# final.net
KiCad netlist of a schematic drawn in EAGLE
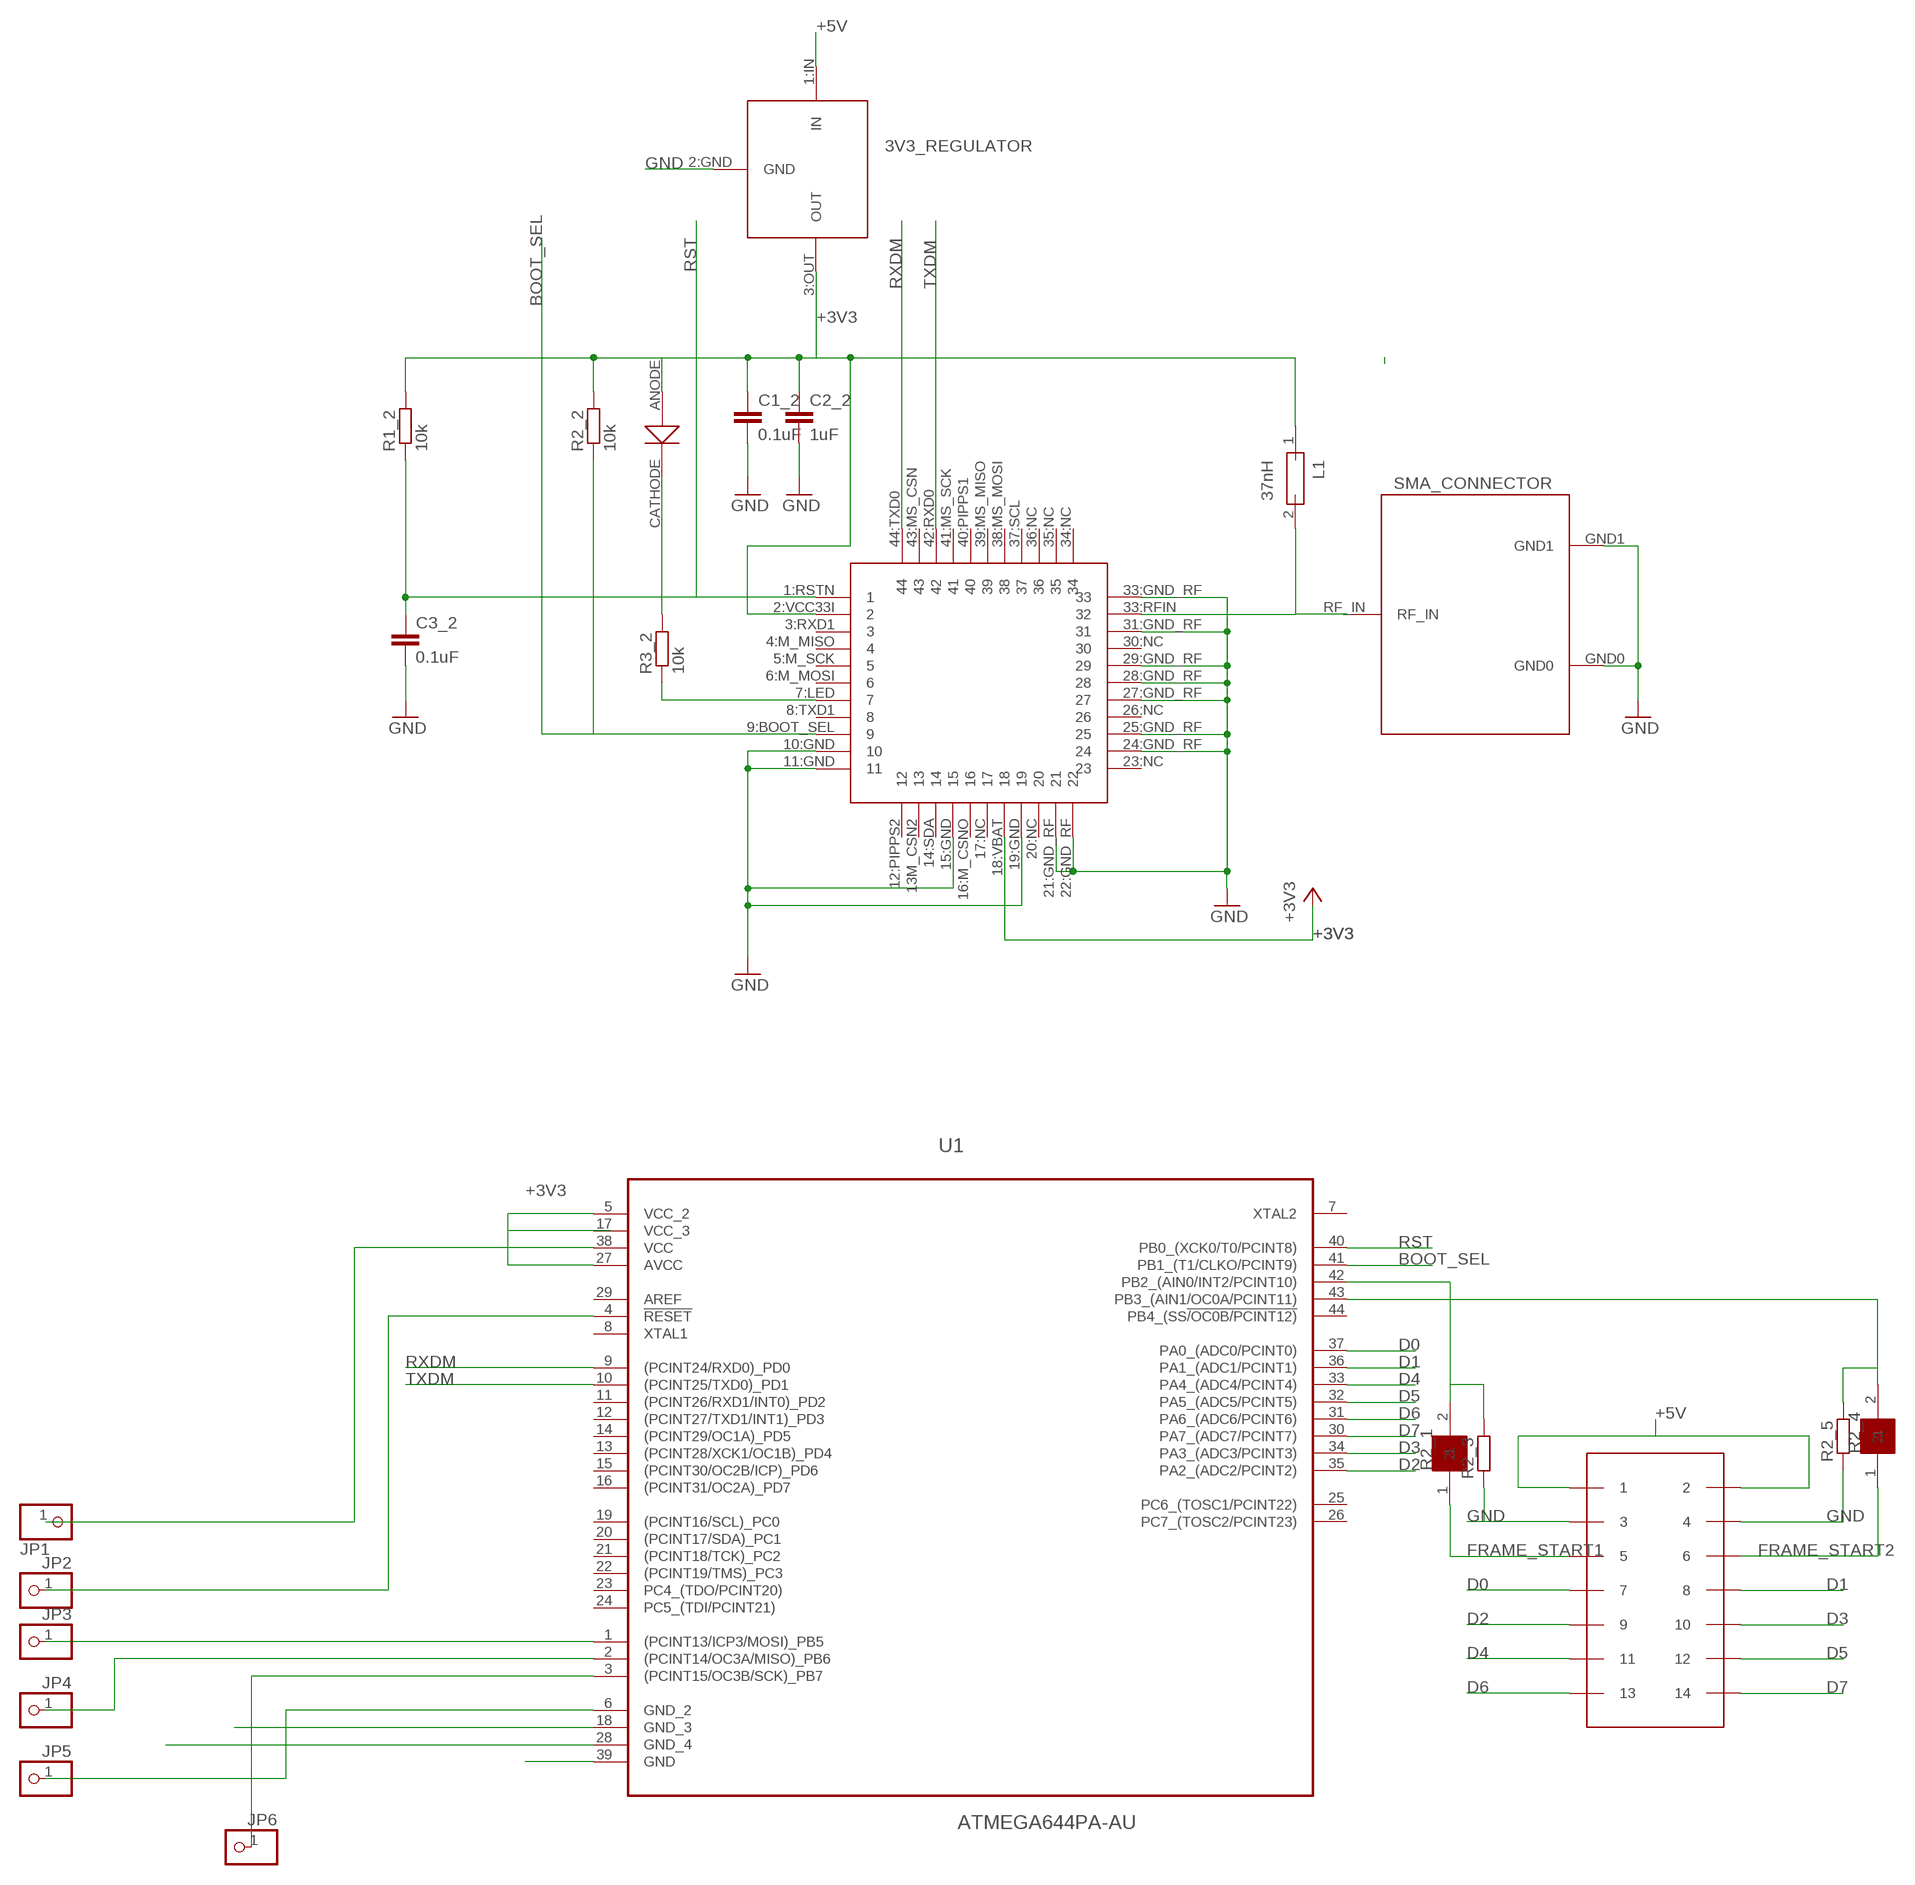
[diagram p0: schematic, sheet 1]

(export (version "E")
  (design (tool "Eeschema 10.0.6"))
  (components
    (comp (ref "3V3_REGULATOR")
      (value "LM3940IT-3.3/NOPB")
      (footprint "eagle-import:3PIN")
      (libsource (lib "eagle-import") (part "LM3940IT-3.3/NOPB"))
    )
    (comp (ref "C1_2")
      (value "0.1uF")
      (footprint "eagle-import:C0402")
      (libsource (lib "eagle-import") (part "C-EUC0402"))
    )
    (comp (ref "C2_2")
      (value "1uF")
      (footprint "eagle-import:C0402")
      (libsource (lib "eagle-import") (part "C-EUC0402"))
    )
    (comp (ref "C3_2")
      (value "0.1uF")
      (footprint "eagle-import:C0402")
      (libsource (lib "eagle-import") (part "C-EUC0402"))
    )
    (comp (ref "GPS_1")
      (value "VENUS838FLPX")
      (footprint "eagle-import:LGA-44")
      (libsource (lib "eagle-import") (part "VENUS838FLPX"))
    )
    (comp (ref "HARWIN_CONNECTOR")
      (value "HARWIN_CONNECTOR")
      (footprint "eagle-import:14DIP")
      (libsource (lib "eagle-import") (part "HARWIN_CONNECTOR"))
    )
    (comp (ref "JP1")
      (value "PINHD-1X1")
      (footprint "eagle-import:1X01")
      (libsource (lib "eagle-import") (part "PINHD-1X1"))
    )
    (comp (ref "JP2")
      (value "PINHD-1X1")
      (footprint "eagle-import:1X01")
      (libsource (lib "eagle-import") (part "PINHD-1X1"))
    )
    (comp (ref "JP3")
      (value "PINHD-1X1")
      (footprint "eagle-import:1X01")
      (libsource (lib "eagle-import") (part "PINHD-1X1"))
    )
    (comp (ref "JP4")
      (value "PINHD-1X1")
      (footprint "eagle-import:1X01")
      (libsource (lib "eagle-import") (part "PINHD-1X1"))
    )
    (comp (ref "JP5")
      (value "PINHD-1X1")
      (footprint "eagle-import:1X01")
      (libsource (lib "eagle-import") (part "PINHD-1X1"))
    )
    (comp (ref "JP6")
      (value "PINHD-1X1")
      (footprint "eagle-import:1X01")
      (libsource (lib "eagle-import") (part "PINHD-1X1"))
    )
    (comp (ref "L1")
      (value "37nH")
      (footprint "eagle-import:0805")
      (libsource (lib "eagle-import") (part "0805_INDUCTOR"))
    )
    (comp (ref "R1_2")
      (value "10k")
      (footprint "eagle-import:R0402")
      (libsource (lib "eagle-import") (part "R-EU_R0402"))
    )
    (comp (ref "R2_1")
      (value "0805RESISTOR")
      (footprint "eagle-import:0805")
      (libsource (lib "eagle-import") (part "0805RESISTOR"))
    )
    (comp (ref "R2_2")
      (value "10k")
      (footprint "eagle-import:R0402")
      (libsource (lib "eagle-import") (part "R-EU_R0402"))
    )
    (comp (ref "R2_3")
      (value "R-EU_R0402")
      (footprint "eagle-import:R0402")
      (libsource (lib "eagle-import") (part "R-EU_R0402"))
    )
    (comp (ref "R2_4")
      (value "0805RESISTOR")
      (footprint "eagle-import:0805")
      (libsource (lib "eagle-import") (part "0805RESISTOR"))
    )
    (comp (ref "R2_5")
      (value "R-EU_R0402")
      (footprint "eagle-import:R0402")
      (libsource (lib "eagle-import") (part "R-EU_R0402"))
    )
    (comp (ref "R3_2")
      (value "10k")
      (footprint "eagle-import:R0402")
      (libsource (lib "eagle-import") (part "R-EU_R0402"))
    )
    (comp (ref "SMA_CONNECTOR")
      (value "SMA_SIDE")
      (footprint "eagle-import:SMA_SIDE")
      (libsource (lib "eagle-import") (part "SMA_SIDE"))
    )
    (comp (ref "U$1")
      (value "HSMH-C190-DIODE")
      (footprint "eagle-import:HSMH-C190-DIODE")
      (libsource (lib "eagle-import") (part "HSMH-C190-DIODE"))
    )
    (comp (ref "U1")
      (value "ATMEGA644PA-AU")
      (footprint "eagle-import:QFP80P1200X1200X120-44N")
      (libsource (lib "eagle-import") (part "ATMEGA644PA-AU"))
    )
  )
  (nets
    (net (code "1") (name "+3V3") (class "Default")
      (node (ref "3V3_REGULATOR") (pin "3:OUT") (pinfunction "OUT_3:OUT") (pintype "bidirectional"))
      (node (ref "C1_2") (pin "1") (pinfunction "1_1") (pintype "passive"))
      (node (ref "C2_2") (pin "1") (pinfunction "1_1") (pintype "passive"))
      (node (ref "GPS_1") (pin "18:VBAT") (pinfunction "18_18:VBAT") (pintype "bidirectional"))
      (node (ref "GPS_1") (pin "2:VCC33I") (pinfunction "2_2:VCC33I") (pintype "bidirectional"))
      (node (ref "JP1") (pin "1") (pinfunction "1_1") (pintype "passive"))
      (node (ref "L1") (pin "1") (pinfunction "1_1") (pintype "bidirectional"))
      (node (ref "R1_2") (pin "2") (pinfunction "2_2") (pintype "passive"))
      (node (ref "R2_2") (pin "2") (pinfunction "2_2") (pintype "passive"))
      (node (ref "U$1") (pin "ANODE") (pinfunction "AN_ANODE") (pintype "bidirectional"))
      (node (ref "U1") (pin "17") (pinfunction "VCC_3_17") (pintype "power_in"))
      (node (ref "U1") (pin "27") (pinfunction "AVCC_27") (pintype "power_in"))
      (node (ref "U1") (pin "38") (pinfunction "VCC_38") (pintype "power_in"))
      (node (ref "U1") (pin "5") (pinfunction "VCC_2_5") (pintype "power_in"))
    )
    (net (code "2") (name "/+5V") (class "Default")
      (node (ref "3V3_REGULATOR") (pin "1:IN") (pinfunction "IN_1:IN") (pintype "bidirectional"))
      (node (ref "HARWIN_CONNECTOR") (pin "1") (pinfunction "1_1") (pintype "bidirectional"))
      (node (ref "HARWIN_CONNECTOR") (pin "2") (pinfunction "2_2") (pintype "bidirectional"))
    )
    (net (code "3") (name "/BOOT_SEL") (class "Default")
      (node (ref "GPS_1") (pin "9:BOOT_SEL") (pinfunction "9_9:BOOT_SEL") (pintype "bidirectional"))
      (node (ref "R2_2") (pin "1") (pinfunction "1_1") (pintype "passive"))
      (node (ref "U1") (pin "41") (pinfunction "PB1_(T1/CLKO/PCINT9)_41") (pintype "bidirectional"))
    )
    (net (code "4") (name "/D0") (class "Default")
      (node (ref "HARWIN_CONNECTOR") (pin "7") (pinfunction "7_7") (pintype "bidirectional"))
      (node (ref "U1") (pin "37") (pinfunction "PA0_(ADC0/PCINT0)_37") (pintype "bidirectional"))
    )
    (net (code "5") (name "/D1") (class "Default")
      (node (ref "HARWIN_CONNECTOR") (pin "8") (pinfunction "8_8") (pintype "bidirectional"))
      (node (ref "U1") (pin "36") (pinfunction "PA1_(ADC1/PCINT1)_36") (pintype "bidirectional"))
    )
    (net (code "6") (name "/D2") (class "Default")
      (node (ref "HARWIN_CONNECTOR") (pin "9") (pinfunction "9_9") (pintype "bidirectional"))
      (node (ref "U1") (pin "35") (pinfunction "PA2_(ADC2/PCINT2)_35") (pintype "bidirectional"))
    )
    (net (code "7") (name "/D3") (class "Default")
      (node (ref "HARWIN_CONNECTOR") (pin "10") (pinfunction "10_10") (pintype "bidirectional"))
      (node (ref "U1") (pin "34") (pinfunction "PA3_(ADC3/PCINT3)_34") (pintype "bidirectional"))
    )
    (net (code "8") (name "/D4") (class "Default")
      (node (ref "HARWIN_CONNECTOR") (pin "11") (pinfunction "11_11") (pintype "bidirectional"))
      (node (ref "U1") (pin "33") (pinfunction "PA4_(ADC4/PCINT4)_33") (pintype "bidirectional"))
    )
    (net (code "9") (name "/D5") (class "Default")
      (node (ref "HARWIN_CONNECTOR") (pin "12") (pinfunction "12_12") (pintype "bidirectional"))
      (node (ref "U1") (pin "32") (pinfunction "PA5_(ADC5/PCINT5)_32") (pintype "bidirectional"))
    )
    (net (code "10") (name "/D6") (class "Default")
      (node (ref "HARWIN_CONNECTOR") (pin "13") (pinfunction "13_13") (pintype "bidirectional"))
      (node (ref "U1") (pin "31") (pinfunction "PA6_(ADC6/PCINT6)_31") (pintype "bidirectional"))
    )
    (net (code "11") (name "/D7") (class "Default")
      (node (ref "HARWIN_CONNECTOR") (pin "14") (pinfunction "14_14") (pintype "bidirectional"))
      (node (ref "U1") (pin "30") (pinfunction "PA7_(ADC7/PCINT7)_30") (pintype "bidirectional"))
    )
    (net (code "12") (name "/FRAME_START1") (class "Default")
      (node (ref "HARWIN_CONNECTOR") (pin "5") (pinfunction "5_5") (pintype "bidirectional"))
      (node (ref "R2_1") (pin "1") (pinfunction "1_1") (pintype "bidirectional"))
    )
    (net (code "13") (name "/FRAME_START2") (class "Default")
      (node (ref "HARWIN_CONNECTOR") (pin "6") (pinfunction "6_6") (pintype "bidirectional"))
      (node (ref "R2_4") (pin "1") (pinfunction "1_1") (pintype "bidirectional"))
    )
    (net (code "14") (name "/RST") (class "Default")
      (node (ref "C3_2") (pin "1") (pinfunction "1_1") (pintype "passive"))
      (node (ref "GPS_1") (pin "1:RSTN") (pinfunction "1_1:RSTN") (pintype "bidirectional"))
      (node (ref "R1_2") (pin "1") (pinfunction "1_1") (pintype "passive"))
      (node (ref "U1") (pin "40") (pinfunction "PB0_(XCK0/T0/PCINT8)_40") (pintype "bidirectional"))
    )
    (net (code "15") (name "/RXDM") (class "Default")
      (node (ref "GPS_1") (pin "44:TXD0") (pinfunction "44_44:TXD0") (pintype "bidirectional"))
      (node (ref "U1") (pin "9") (pinfunction "(PCINT24/RXD0)_PD0_9") (pintype "bidirectional"))
    )
    (net (code "16") (name "/TXDM") (class "Default")
      (node (ref "GPS_1") (pin "42:RXD0") (pinfunction "42_42:RXD0") (pintype "bidirectional"))
      (node (ref "U1") (pin "10") (pinfunction "(PCINT25/TXD0)_PD1_10") (pintype "bidirectional"))
    )
    (net (code "17") (name "GND") (class "Default")
      (node (ref "3V3_REGULATOR") (pin "2:GND") (pinfunction "GND_2:GND") (pintype "bidirectional"))
      (node (ref "C1_2") (pin "2") (pinfunction "2_2") (pintype "passive"))
      (node (ref "C2_2") (pin "2") (pinfunction "2_2") (pintype "passive"))
      (node (ref "C3_2") (pin "2") (pinfunction "2_2") (pintype "passive"))
      (node (ref "GPS_1") (pin "10:GND") (pinfunction "10_10:GND") (pintype "bidirectional"))
      (node (ref "GPS_1") (pin "11:GND") (pinfunction "11_11:GND") (pintype "bidirectional"))
      (node (ref "GPS_1") (pin "15:GND") (pinfunction "15_15:GND") (pintype "bidirectional"))
      (node (ref "GPS_1") (pin "19:GND") (pinfunction "19_19:GND") (pintype "bidirectional"))
      (node (ref "GPS_1") (pin "21:GND_RF") (pinfunction "21_21:GND_RF") (pintype "bidirectional"))
      (node (ref "GPS_1") (pin "22:GND_RF") (pinfunction "22_22:GND_RF") (pintype "bidirectional"))
      (node (ref "GPS_1") (pin "24:GND_RF") (pinfunction "24_24:GND_RF") (pintype "bidirectional"))
      (node (ref "GPS_1") (pin "25:GND_RF") (pinfunction "25_25:GND_RF") (pintype "bidirectional"))
      (node (ref "GPS_1") (pin "27:GND_RF") (pinfunction "27_27:GND_RF") (pintype "bidirectional"))
      (node (ref "GPS_1") (pin "28:GND_RF") (pinfunction "28_28:GND_RF") (pintype "bidirectional"))
      (node (ref "GPS_1") (pin "29:GND_RF") (pinfunction "29_29:GND_RF") (pintype "bidirectional"))
      (node (ref "GPS_1") (pin "31:GND_RF") (pinfunction "31_31:GND_RF") (pintype "bidirectional"))
      (node (ref "GPS_1") (pin "33:GND_RF") (pinfunction "33_33:GND_RF") (pintype "bidirectional"))
      (node (ref "HARWIN_CONNECTOR") (pin "3") (pinfunction "3_3") (pintype "bidirectional"))
      (node (ref "HARWIN_CONNECTOR") (pin "4") (pinfunction "4_4") (pintype "bidirectional"))
      (node (ref "JP5") (pin "1") (pinfunction "1_1") (pintype "passive"))
      (node (ref "R2_3") (pin "1") (pinfunction "1_1") (pintype "passive"))
      (node (ref "R2_5") (pin "1") (pinfunction "1_1") (pintype "passive"))
      (node (ref "SMA_CONNECTOR") (pin "GND0") (pinfunction "GND0_GND0") (pintype "bidirectional"))
      (node (ref "SMA_CONNECTOR") (pin "GND1") (pinfunction "GND1_GND1") (pintype "bidirectional"))
      (node (ref "U1") (pin "18") (pinfunction "GND_3_18") (pintype "passive"))
      (node (ref "U1") (pin "28") (pinfunction "GND_4_28") (pintype "passive"))
      (node (ref "U1") (pin "39") (pinfunction "GND_39") (pintype "passive"))
      (node (ref "U1") (pin "6") (pinfunction "GND_2_6") (pintype "passive"))
    )
    (net (code "18") (name "Net-(GPS_1-7)") (class "Default")
      (node (ref "GPS_1") (pin "7:LED") (pinfunction "7_7:LED") (pintype "bidirectional"))
      (node (ref "R3_2") (pin "1") (pinfunction "1_1") (pintype "passive"))
    )
    (net (code "19") (name "Net-(GPS_1-32)") (class "Default")
      (node (ref "GPS_1") (pin "33:RFIN") (pinfunction "32_33:RFIN") (pintype "bidirectional"))
      (node (ref "L1") (pin "2") (pinfunction "2_2") (pintype "bidirectional"))
      (node (ref "SMA_CONNECTOR") (pin "RF_IN") (pinfunction "RF_IN_RF_IN") (pintype "bidirectional"))
    )
    (net (code "20") (name "Net-(U$1-CATH)") (class "Default")
      (node (ref "R3_2") (pin "2") (pinfunction "2_2") (pintype "passive"))
      (node (ref "U$1") (pin "CATHODE") (pinfunction "CATH_CATHODE") (pintype "bidirectional"))
    )
    (net (code "21") (name "Net-(U1-(PCINT13{slash}ICP3{slash}MOSI)_PB5)") (class "Default")
      (node (ref "JP3") (pin "1") (pinfunction "1_1") (pintype "passive"))
      (node (ref "U1") (pin "1") (pinfunction "(PCINT13/ICP3/MOSI)_PB5_1") (pintype "bidirectional"))
    )
    (net (code "22") (name "Net-(U1-(PCINT14{slash}OC3A{slash}MISO)_PB6)") (class "Default")
      (node (ref "JP4") (pin "1") (pinfunction "1_1") (pintype "passive"))
      (node (ref "U1") (pin "2") (pinfunction "(PCINT14/OC3A/MISO)_PB6_2") (pintype "bidirectional"))
    )
    (net (code "23") (name "Net-(U1-(PCINT15{slash}OC3B{slash}SCK)_PB7)") (class "Default")
      (node (ref "JP6") (pin "1") (pinfunction "1_1") (pintype "passive"))
      (node (ref "U1") (pin "3") (pinfunction "(PCINT15/OC3B/SCK)_PB7_3") (pintype "bidirectional"))
    )
    (net (code "24") (name "Net-(U1-PB2_(AIN0{slash}INT2{slash}PCINT10))") (class "Default")
      (node (ref "R2_1") (pin "2") (pinfunction "2_2") (pintype "bidirectional"))
      (node (ref "R2_3") (pin "2") (pinfunction "2_2") (pintype "passive"))
      (node (ref "U1") (pin "42") (pinfunction "PB2_(AIN0/INT2/PCINT10)_42") (pintype "bidirectional"))
    )
    (net (code "25") (name "Net-(U1-PB3_(AIN1{slash}OC0A{slash}PCINT11))") (class "Default")
      (node (ref "R2_4") (pin "2") (pinfunction "2_2") (pintype "bidirectional"))
      (node (ref "R2_5") (pin "2") (pinfunction "2_2") (pintype "passive"))
      (node (ref "U1") (pin "43") (pinfunction "PB3_(AIN1/OC0A/PCINT11)_43") (pintype "bidirectional"))
    )
    (net (code "26") (name "Net-(U1-~{RESET})") (class "Default")
      (node (ref "JP2") (pin "1") (pinfunction "1_1") (pintype "passive"))
      (node (ref "U1") (pin "4") (pinfunction "~{RESET}_4") (pintype "input"))
    )
    (net (code "27") (name "unconnected-(GPS_1-3-Pad3:RXD1)") (class "Default")
      (node (ref "GPS_1") (pin "3:RXD1") (pinfunction "3_3:RXD1") (pintype "bidirectional"))
    )
    (net (code "28") (name "unconnected-(GPS_1-4-Pad4:M_MISO)") (class "Default")
      (node (ref "GPS_1") (pin "4:M_MISO") (pinfunction "4_4:M_MISO") (pintype "bidirectional"))
    )
    (net (code "29") (name "unconnected-(GPS_1-5-Pad5:M_SCK)") (class "Default")
      (node (ref "GPS_1") (pin "5:M_SCK") (pinfunction "5_5:M_SCK") (pintype "bidirectional"))
    )
    (net (code "30") (name "unconnected-(GPS_1-6-Pad6:M_MOSI)") (class "Default")
      (node (ref "GPS_1") (pin "6:M_MOSI") (pinfunction "6_6:M_MOSI") (pintype "bidirectional"))
    )
    (net (code "31") (name "unconnected-(GPS_1-8-Pad8:TXD1)") (class "Default")
      (node (ref "GPS_1") (pin "8:TXD1") (pinfunction "8_8:TXD1") (pintype "bidirectional"))
    )
    (net (code "32") (name "unconnected-(GPS_1-12-Pad12:PIPPS2)") (class "Default")
      (node (ref "GPS_1") (pin "12:PIPPS2") (pinfunction "12_12:PIPPS2") (pintype "bidirectional"))
    )
    (net (code "33") (name "unconnected-(GPS_1-13-Pad13M_CSN2)") (class "Default")
      (node (ref "GPS_1") (pin "13M_CSN2") (pinfunction "13_13M_CSN2") (pintype "bidirectional"))
    )
    (net (code "34") (name "unconnected-(GPS_1-14-Pad14:SDA)") (class "Default")
      (node (ref "GPS_1") (pin "14:SDA") (pinfunction "14_14:SDA") (pintype "bidirectional"))
    )
    (net (code "35") (name "unconnected-(GPS_1-16-Pad16:M_CSNO)") (class "Default")
      (node (ref "GPS_1") (pin "16:M_CSNO") (pinfunction "16_16:M_CSNO") (pintype "bidirectional"))
    )
    (net (code "36") (name "unconnected-(GPS_1-17-Pad17:NC)") (class "Default")
      (node (ref "GPS_1") (pin "17:NC") (pinfunction "17_17:NC") (pintype "bidirectional"))
    )
    (net (code "37") (name "unconnected-(GPS_1-20-Pad20:NC)") (class "Default")
      (node (ref "GPS_1") (pin "20:NC") (pinfunction "20_20:NC") (pintype "bidirectional"))
    )
    (net (code "38") (name "unconnected-(GPS_1-23-Pad23:NC)") (class "Default")
      (node (ref "GPS_1") (pin "23:NC") (pinfunction "23_23:NC") (pintype "bidirectional"))
    )
    (net (code "39") (name "unconnected-(GPS_1-26-Pad26:NC)") (class "Default")
      (node (ref "GPS_1") (pin "26:NC") (pinfunction "26_26:NC") (pintype "bidirectional"))
    )
    (net (code "40") (name "unconnected-(GPS_1-30-Pad30:NC)") (class "Default")
      (node (ref "GPS_1") (pin "30:NC") (pinfunction "30_30:NC") (pintype "bidirectional"))
    )
    (net (code "41") (name "unconnected-(GPS_1-34-Pad34:NC)") (class "Default")
      (node (ref "GPS_1") (pin "34:NC") (pinfunction "34_34:NC") (pintype "bidirectional"))
    )
    (net (code "42") (name "unconnected-(GPS_1-35-Pad35:NC)") (class "Default")
      (node (ref "GPS_1") (pin "35:NC") (pinfunction "35_35:NC") (pintype "bidirectional"))
    )
    (net (code "43") (name "unconnected-(GPS_1-36-Pad36:NC)") (class "Default")
      (node (ref "GPS_1") (pin "36:NC") (pinfunction "36_36:NC") (pintype "bidirectional"))
    )
    (net (code "44") (name "unconnected-(GPS_1-37-Pad37:SCL)") (class "Default")
      (node (ref "GPS_1") (pin "37:SCL") (pinfunction "37_37:SCL") (pintype "bidirectional"))
    )
    (net (code "45") (name "unconnected-(GPS_1-38-Pad38:MS_MOSI)") (class "Default")
      (node (ref "GPS_1") (pin "38:MS_MOSI") (pinfunction "38_38:MS_MOSI") (pintype "bidirectional"))
    )
    (net (code "46") (name "unconnected-(GPS_1-39-Pad39:MS_MISO)") (class "Default")
      (node (ref "GPS_1") (pin "39:MS_MISO") (pinfunction "39_39:MS_MISO") (pintype "bidirectional"))
    )
    (net (code "47") (name "unconnected-(GPS_1-40-Pad40:PIPPS1)") (class "Default")
      (node (ref "GPS_1") (pin "40:PIPPS1") (pinfunction "40_40:PIPPS1") (pintype "bidirectional"))
    )
    (net (code "48") (name "unconnected-(GPS_1-41-Pad41:MS_SCK)") (class "Default")
      (node (ref "GPS_1") (pin "41:MS_SCK") (pinfunction "41_41:MS_SCK") (pintype "bidirectional"))
    )
    (net (code "49") (name "unconnected-(GPS_1-43-Pad43:MS_CSN)") (class "Default")
      (node (ref "GPS_1") (pin "43:MS_CSN") (pinfunction "43_43:MS_CSN") (pintype "bidirectional"))
    )
    (net (code "50") (name "unconnected-(U1-(PCINT16{slash}SCL)_PC0-Pad19)") (class "Default")
      (node (ref "U1") (pin "19") (pinfunction "(PCINT16/SCL)_PC0_19") (pintype "bidirectional"))
    )
    (net (code "51") (name "unconnected-(U1-(PCINT17{slash}SDA)_PC1-Pad20)") (class "Default")
      (node (ref "U1") (pin "20") (pinfunction "(PCINT17/SDA)_PC1_20") (pintype "bidirectional"))
    )
    (net (code "52") (name "unconnected-(U1-(PCINT18{slash}TCK)_PC2-Pad21)") (class "Default")
      (node (ref "U1") (pin "21") (pinfunction "(PCINT18/TCK)_PC2_21") (pintype "bidirectional"))
    )
    (net (code "53") (name "unconnected-(U1-(PCINT19{slash}TMS)_PC3-Pad22)") (class "Default")
      (node (ref "U1") (pin "22") (pinfunction "(PCINT19/TMS)_PC3_22") (pintype "bidirectional"))
    )
    (net (code "54") (name "unconnected-(U1-(PCINT26{slash}RXD1{slash}INT0)_PD2-Pad11)") (class "Default")
      (node (ref "U1") (pin "11") (pinfunction "(PCINT26/RXD1/INT0)_PD2_11") (pintype "bidirectional"))
    )
    (net (code "55") (name "unconnected-(U1-(PCINT27{slash}TXD1{slash}INT1)_PD3-Pad12)") (class "Default")
      (node (ref "U1") (pin "12") (pinfunction "(PCINT27/TXD1/INT1)_PD3_12") (pintype "bidirectional"))
    )
    (net (code "56") (name "unconnected-(U1-(PCINT28{slash}XCK1{slash}OC1B)_PD4-Pad13)") (class "Default")
      (node (ref "U1") (pin "13") (pinfunction "(PCINT28/XCK1/OC1B)_PD4_13") (pintype "bidirectional"))
    )
    (net (code "57") (name "unconnected-(U1-(PCINT29{slash}OC1A)_PD5-Pad14)") (class "Default")
      (node (ref "U1") (pin "14") (pinfunction "(PCINT29/OC1A)_PD5_14") (pintype "bidirectional"))
    )
    (net (code "58") (name "unconnected-(U1-(PCINT30{slash}OC2B{slash}ICP)_PD6-Pad15)") (class "Default")
      (node (ref "U1") (pin "15") (pinfunction "(PCINT30/OC2B/ICP)_PD6_15") (pintype "bidirectional"))
    )
    (net (code "59") (name "unconnected-(U1-(PCINT31{slash}OC2A)_PD7-Pad16)") (class "Default")
      (node (ref "U1") (pin "16") (pinfunction "(PCINT31/OC2A)_PD7_16") (pintype "bidirectional"))
    )
    (net (code "60") (name "unconnected-(U1-AREF-Pad29)") (class "Default")
      (node (ref "U1") (pin "29") (pinfunction "AREF_29") (pintype "passive"))
    )
    (net (code "61") (name "unconnected-(U1-PB4_(SS~{{slash}OC0B{slash}PCINT12})-Pad44)") (class "Default")
      (node (ref "U1") (pin "44") (pinfunction "PB4_(SS~{/OC0B/PCINT12})_44") (pintype "bidirectional"))
    )
    (net (code "62") (name "unconnected-(U1-PC4_(TDO{slash}PCINT20)-Pad23)") (class "Default")
      (node (ref "U1") (pin "23") (pinfunction "PC4_(TDO/PCINT20)_23") (pintype "bidirectional"))
    )
    (net (code "63") (name "unconnected-(U1-PC5_(TDI{slash}PCINT21)-Pad24)") (class "Default")
      (node (ref "U1") (pin "24") (pinfunction "PC5_(TDI/PCINT21)_24") (pintype "bidirectional"))
    )
    (net (code "64") (name "unconnected-(U1-PC6_(TOSC1{slash}PCINT22)-Pad25)") (class "Default")
      (node (ref "U1") (pin "25") (pinfunction "PC6_(TOSC1/PCINT22)_25") (pintype "bidirectional"))
    )
    (net (code "65") (name "unconnected-(U1-PC7_(TOSC2{slash}PCINT23)-Pad26)") (class "Default")
      (node (ref "U1") (pin "26") (pinfunction "PC7_(TOSC2/PCINT23)_26") (pintype "bidirectional"))
    )
    (net (code "66") (name "unconnected-(U1-XTAL1-Pad8)") (class "Default")
      (node (ref "U1") (pin "8") (pinfunction "XTAL1_8") (pintype "input"))
    )
    (net (code "67") (name "unconnected-(U1-XTAL2-Pad7)") (class "Default")
      (node (ref "U1") (pin "7") (pinfunction "XTAL2_7") (pintype "output"))
    )
  )
)
